# Miniproj.net
KiCad netlist of a schematic drawn in Altium Designer
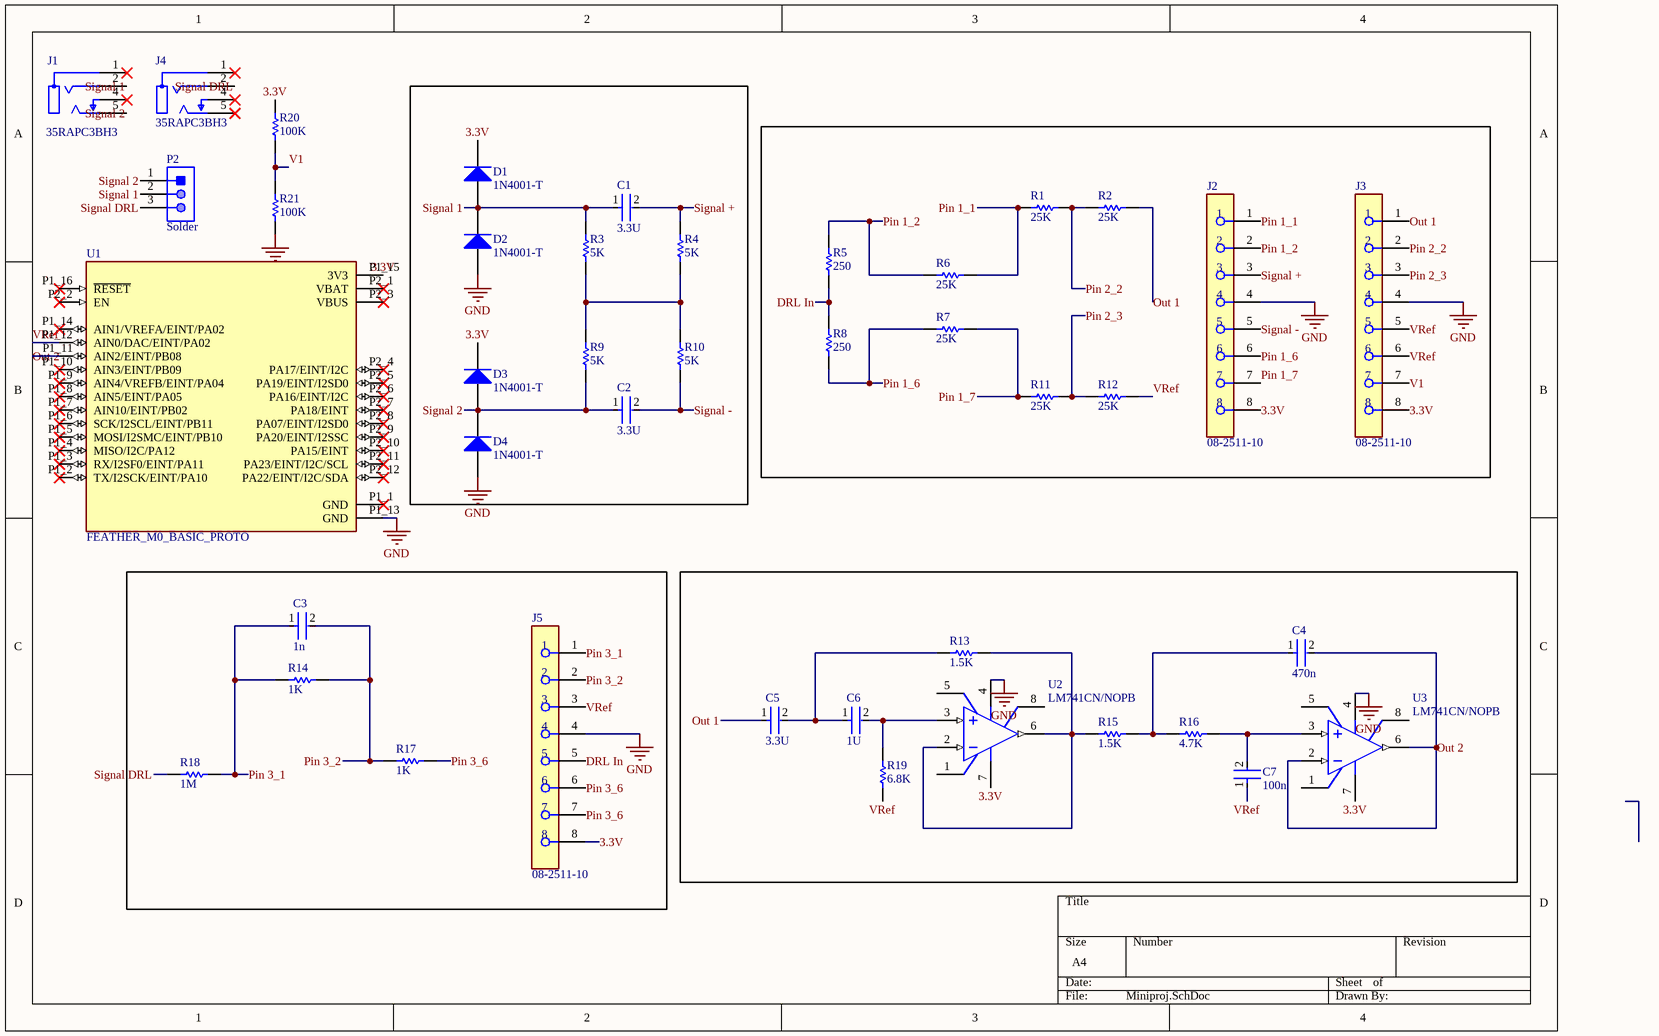
[diagram p0: Miniproj.SchDoc]

(export (version "E")
  (design (tool "Eeschema 10.0.6"))
  (components
    (comp (ref "C1")
      (value "3.3U")
      (footprint "FP-RCE3DB-MFG")
      (description "Cap Ceramic 10uF 25V X7R ±10% Radial 2.5mm +125°C Automotive Ammo Pack")
      (fields (field (name "TOLERANCE") "10%"))
      (libsource (lib "Altium Content Vault") (part "b4654b650e69147ec39a6b967a45e02"))
    )
    (comp (ref "C2")
      (value "3.3U")
      (footprint "FP-RCE3DB-MFG")
      (description "Cap Ceramic 10uF 25V X7R ±10% Radial 2.5mm +125°C Automotive Ammo Pack")
      (fields (field (name "TOLERANCE") "10%"))
      (libsource (lib "Altium Content Vault") (part "b4654b650e69147ec39a6b967a45e02"))
    )
    (comp (ref "C3")
      (value "1n")
      (footprint "FP-RCE3DB-MFG")
      (description "Cap Ceramic 10uF 25V X7R ±10% Radial 2.5mm +125°C Automotive Ammo Pack")
      (fields (field (name "TOLERANCE") "10%"))
      (libsource (lib "Altium Content Vault") (part "b4654b650e69147ec39a6b967a45e02"))
    )
    (comp (ref "C4")
      (value "470n")
      (footprint "FP-RCE3DB-MFG")
      (description "Cap Ceramic 10uF 25V X7R ±10% Radial 2.5mm +125°C Automotive Ammo Pack")
      (fields (field (name "TOLERANCE") "10%"))
      (libsource (lib "Altium Content Vault") (part "b4654b650e69147ec39a6b967a45e02"))
    )
    (comp (ref "C5")
      (value "3.3U")
      (footprint "FP-RCE3DB-MFG")
      (description "Cap Ceramic 10uF 25V X7R ±10% Radial 2.5mm +125°C Automotive Ammo Pack")
      (fields (field (name "TOLERANCE") "10%"))
      (libsource (lib "Altium Content Vault") (part "b4654b650e69147ec39a6b967a45e02"))
    )
    (comp (ref "C6")
      (value "1U")
      (footprint "FP-RCE3DB-MFG")
      (description "Cap Ceramic 10uF 25V X7R ±10% Radial 2.5mm +125°C Automotive Ammo Pack")
      (fields (field (name "TOLERANCE") "10%"))
      (libsource (lib "Altium Content Vault") (part "b4654b650e69147ec39a6b967a45e02"))
    )
    (comp (ref "C7")
      (value "100n")
      (footprint "FP-RCE3DB-MFG")
      (description "Cap Ceramic 10uF 25V X7R ±10% Radial 2.5mm +125°C Automotive Ammo Pack")
      (fields (field (name "TOLERANCE") "10%"))
      (libsource (lib "Altium Content Vault") (part "b4654b650e69147ec39a6b967a45e02"))
    )
    (comp (ref "D1")
      (value "1N4001-T")
      (footprint "DIOD-DO-41-P-2_V")
      (description "1.0 A Rectifier, 15 pF, 50 V, -65 to 150 degC, 2-Pin DO-41 Plastic, RoHS, Tape and Reel")
      (fields (field (name "MANUFACTURER") "Diodes Inc"))
      (libsource (lib "Altium Content Vault") (part "DIOD-D-A1K2-2"))
    )
    (comp (ref "D2")
      (value "1N4001-T")
      (footprint "DIOD-DO-41-P-2_V")
      (description "1.0 A Rectifier, 15 pF, 50 V, -65 to 150 degC, 2-Pin DO-41 Plastic, RoHS, Tape and Reel")
      (fields (field (name "MANUFACTURER") "Diodes Inc"))
      (libsource (lib "Altium Content Vault") (part "DIOD-D-A1K2-2"))
    )
    (comp (ref "D3")
      (value "1N4001-T")
      (footprint "DIOD-DO-41-P-2_V")
      (description "1.0 A Rectifier, 15 pF, 50 V, -65 to 150 degC, 2-Pin DO-41 Plastic, RoHS, Tape and Reel")
      (fields (field (name "MANUFACTURER") "Diodes Inc"))
      (libsource (lib "Altium Content Vault") (part "DIOD-D-A1K2-2"))
    )
    (comp (ref "D4")
      (value "1N4001-T")
      (footprint "DIOD-DO-41-P-2_V")
      (description "1.0 A Rectifier, 15 pF, 50 V, -65 to 150 degC, 2-Pin DO-41 Plastic, RoHS, Tape and Reel")
      (fields (field (name "MANUFACTURER") "Diodes Inc"))
      (libsource (lib "Altium Content Vault") (part "DIOD-D-A1K2-2"))
    )
    (comp (ref "J1")
      (value "35RAPC3BH3")
      (footprint "FP-35RAPC3BH3-MFG")
      (description "CONN JACK STEREO 3.5MM R/A")
      (libsource (lib "Altium Content Vault") (part "6593a1246df2d7246a2ad7da18ee256"))
    )
    (comp (ref "J2")
      (value "08-2511-10")
      (footprint "FP-08-2511-10-MFG")
      (description "CONN IC DIP SOCKET 8POS TIN")
      (fields
        (field (name "MANUFACTURER") "Aries Electronics")
        (field (name "OCTOPART") "https://octopart.com/08-2511-10-aries-767661")
      )
      (libsource (lib "Altium Content Vault") (part "b0a0b555dd3abf3683e7c330df25cc4"))
    )
    (comp (ref "J3")
      (value "08-2511-10")
      (footprint "FP-08-2511-10-MFG")
      (description "CONN IC DIP SOCKET 8POS TIN")
      (fields
        (field (name "MANUFACTURER") "Aries Electronics")
        (field (name "OCTOPART") "https://octopart.com/08-2511-10-aries-767661")
      )
      (libsource (lib "Altium Content Vault") (part "b0a0b555dd3abf3683e7c330df25cc4"))
    )
    (comp (ref "J4")
      (value "35RAPC3BH3")
      (footprint "FP-35RAPC3BH3-MFG")
      (description "CONN JACK STEREO 3.5MM R/A")
      (libsource (lib "Altium Content Vault") (part "6593a1246df2d7246a2ad7da18ee256"))
    )
    (comp (ref "J5")
      (value "08-2511-10")
      (footprint "FP-08-2511-10-MFG")
      (description "CONN IC DIP SOCKET 8POS TIN")
      (fields
        (field (name "MANUFACTURER") "Aries Electronics")
        (field (name "OCTOPART") "https://octopart.com/08-2511-10-aries-767661")
      )
      (libsource (lib "Altium Content Vault") (part "b0a0b555dd3abf3683e7c330df25cc4"))
    )
    (comp (ref "P2")
      (value "Solder")
      (footprint "JST-B3B-PH-K-S-3_V")
      (fields (field (name "MANUFACTURER") "JST"))
      (libsource (lib "Altium Content Vault") (part "CN-1P-M-R3"))
    )
    (comp (ref "R1")
      (value "25K")
      (footprint "RESA60-630X240")
      (description "Axial Resistor, 1 KOhm, +/- 1%, 250 mW, -55 to 155 degC, 2-Pin THD, RoHS, Bulk")
      (fields (field (name "TOLERANCE") "1%"))
      (libsource (lib "Altium Content Vault") (part "RES-2"))
    )
    (comp (ref "R2")
      (value "25K")
      (footprint "RESA60-630X240")
      (description "Axial Resistor, 1 KOhm, +/- 1%, 250 mW, -55 to 155 degC, 2-Pin THD, RoHS, Bulk")
      (fields (field (name "TOLERANCE") "1%"))
      (libsource (lib "Altium Content Vault") (part "RES-2"))
    )
    (comp (ref "R3")
      (value "5K")
      (footprint "RESA60-630X240")
      (description "Axial Resistor, 1 KOhm, +/- 1%, 250 mW, -55 to 155 degC, 2-Pin THD, RoHS, Bulk")
      (fields (field (name "TOLERANCE") "1%"))
      (libsource (lib "Altium Content Vault") (part "RES-2"))
    )
    (comp (ref "R4")
      (value "5K")
      (footprint "RESA60-630X240")
      (description "Axial Resistor, 1 KOhm, +/- 1%, 250 mW, -55 to 155 degC, 2-Pin THD, RoHS, Bulk")
      (fields (field (name "TOLERANCE") "1%"))
      (libsource (lib "Altium Content Vault") (part "RES-2"))
    )
    (comp (ref "R5")
      (value "250")
      (footprint "RESA60-630X240")
      (description "Axial Resistor, 1 KOhm, +/- 1%, 250 mW, -55 to 155 degC, 2-Pin THD, RoHS, Bulk")
      (fields (field (name "TOLERANCE") "1%"))
      (libsource (lib "Altium Content Vault") (part "RES-2"))
    )
    (comp (ref "R6")
      (value "25K")
      (footprint "RESA60-630X240")
      (description "Axial Resistor, 1 KOhm, +/- 1%, 250 mW, -55 to 155 degC, 2-Pin THD, RoHS, Bulk")
      (fields (field (name "TOLERANCE") "1%"))
      (libsource (lib "Altium Content Vault") (part "RES-2"))
    )
    (comp (ref "R7")
      (value "25K")
      (footprint "RESA60-630X240")
      (description "Axial Resistor, 1 KOhm, +/- 1%, 250 mW, -55 to 155 degC, 2-Pin THD, RoHS, Bulk")
      (fields (field (name "TOLERANCE") "1%"))
      (libsource (lib "Altium Content Vault") (part "RES-2"))
    )
    (comp (ref "R8")
      (value "250")
      (footprint "RESA60-630X240")
      (description "Axial Resistor, 1 KOhm, +/- 1%, 250 mW, -55 to 155 degC, 2-Pin THD, RoHS, Bulk")
      (fields (field (name "TOLERANCE") "1%"))
      (libsource (lib "Altium Content Vault") (part "RES-2"))
    )
    (comp (ref "R9")
      (value "5K")
      (footprint "RESA60-630X240")
      (description "Axial Resistor, 1 KOhm, +/- 1%, 250 mW, -55 to 155 degC, 2-Pin THD, RoHS, Bulk")
      (fields (field (name "TOLERANCE") "1%"))
      (libsource (lib "Altium Content Vault") (part "RES-2"))
    )
    (comp (ref "R10")
      (value "5K")
      (footprint "RESA60-630X240")
      (description "Axial Resistor, 1 KOhm, +/- 1%, 250 mW, -55 to 155 degC, 2-Pin THD, RoHS, Bulk")
      (fields (field (name "TOLERANCE") "1%"))
      (libsource (lib "Altium Content Vault") (part "RES-2"))
    )
    (comp (ref "R11")
      (value "25K")
      (footprint "RESA60-630X240")
      (description "Axial Resistor, 1 KOhm, +/- 1%, 250 mW, -55 to 155 degC, 2-Pin THD, RoHS, Bulk")
      (fields (field (name "TOLERANCE") "1%"))
      (libsource (lib "Altium Content Vault") (part "RES-2"))
    )
    (comp (ref "R12")
      (value "25K")
      (footprint "RESA60-630X240")
      (description "Axial Resistor, 1 KOhm, +/- 1%, 250 mW, -55 to 155 degC, 2-Pin THD, RoHS, Bulk")
      (fields (field (name "TOLERANCE") "1%"))
      (libsource (lib "Altium Content Vault") (part "RES-2"))
    )
    (comp (ref "R13")
      (value "1.5K")
      (footprint "RESA60-630X240")
      (description "Axial Resistor, 1 KOhm, +/- 1%, 250 mW, -55 to 155 degC, 2-Pin THD, RoHS, Bulk")
      (fields (field (name "TOLERANCE") "1%"))
      (libsource (lib "Altium Content Vault") (part "RES-2"))
    )
    (comp (ref "R14")
      (value "1K")
      (footprint "RESA60-630X240")
      (description "Axial Resistor, 1 KOhm, +/- 1%, 250 mW, -55 to 155 degC, 2-Pin THD, RoHS, Bulk")
      (fields (field (name "TOLERANCE") "1%"))
      (libsource (lib "Altium Content Vault") (part "RES-2"))
    )
    (comp (ref "R15")
      (value "1.5K")
      (footprint "RESA60-630X240")
      (description "Axial Resistor, 1 KOhm, +/- 1%, 250 mW, -55 to 155 degC, 2-Pin THD, RoHS, Bulk")
      (fields (field (name "TOLERANCE") "1%"))
      (libsource (lib "Altium Content Vault") (part "RES-2"))
    )
    (comp (ref "R16")
      (value "4.7K")
      (footprint "RESA60-630X240")
      (description "Axial Resistor, 1 KOhm, +/- 1%, 250 mW, -55 to 155 degC, 2-Pin THD, RoHS, Bulk")
      (fields (field (name "TOLERANCE") "1%"))
      (libsource (lib "Altium Content Vault") (part "RES-2"))
    )
    (comp (ref "R17")
      (value "1K")
      (footprint "RESA60-630X240")
      (description "Axial Resistor, 1 KOhm, +/- 1%, 250 mW, -55 to 155 degC, 2-Pin THD, RoHS, Bulk")
      (fields (field (name "TOLERANCE") "1%"))
      (libsource (lib "Altium Content Vault") (part "RES-2"))
    )
    (comp (ref "R18")
      (value "1M")
      (footprint "RESA60-630X240")
      (description "Axial Resistor, 1 KOhm, +/- 1%, 250 mW, -55 to 155 degC, 2-Pin THD, RoHS, Bulk")
      (fields (field (name "TOLERANCE") "1%"))
      (libsource (lib "Altium Content Vault") (part "RES-2"))
    )
    (comp (ref "R19")
      (value "6.8K")
      (footprint "RESA60-630X240")
      (description "Axial Resistor, 1 KOhm, +/- 1%, 250 mW, -55 to 155 degC, 2-Pin THD, RoHS, Bulk")
      (fields (field (name "TOLERANCE") "1%"))
      (libsource (lib "Altium Content Vault") (part "RES-2"))
    )
    (comp (ref "R20")
      (value "100K")
      (footprint "RESA60-630X240")
      (description "Axial Resistor, 1 KOhm, +/- 1%, 250 mW, -55 to 155 degC, 2-Pin THD, RoHS, Bulk")
      (fields (field (name "TOLERANCE") "1%"))
      (libsource (lib "Altium Content Vault") (part "RES-2"))
    )
    (comp (ref "R21")
      (value "100K")
      (footprint "RESA60-630X240")
      (description "Axial Resistor, 1 KOhm, +/- 1%, 250 mW, -55 to 155 degC, 2-Pin THD, RoHS, Bulk")
      (fields (field (name "TOLERANCE") "1%"))
      (libsource (lib "Altium Content Vault") (part "RES-2"))
    )
    (comp (ref "U1")
      (value "FEATHER_M0_BASIC_PROTO")
      (footprint "MODULE_FEATHER_M0_BASIC_PROTO")
      (description "ATSAMD21G18 Feather M0 Basic Proto series ARM® Cortex®-M0+ MCU 32-Bit Embedded Evaluation Board")
      (fields (field (name "MF") "Adafruit Industries") (field (name "MP") "Feather M0 Basic Proto"))
      (libsource (lib "mini_project_one_rail") (part "CMP-003-000000-1"))
    )
    (comp (ref "U2")
      (value "LM741CN/NOPB")
      (footprint "P0008A")
      (description "Operational Amplifier, 8-pin MDIP, Pb-Free")
      (fields (field (name "MANUFACTURER") "Texas Instruments"))
      (libsource (lib "Altium Content Vault") (part "AMP-OPA-LM741-8"))
    )
    (comp (ref "U3")
      (value "LM741CN/NOPB")
      (footprint "P0008A")
      (description "Operational Amplifier, 8-pin MDIP, Pb-Free")
      (fields (field (name "MANUFACTURER") "Texas Instruments"))
      (libsource (lib "Altium Content Vault") (part "AMP-OPA-LM741-8"))
    )
  )
  (nets
    (net (code "1") (name "/3.3V") (class "Default")
      (node (ref "D1") (pin "2") (pinfunction "K_2") (pintype "passive"))
      (node (ref "D3") (pin "2") (pinfunction "K_2") (pintype "passive"))
      (node (ref "J2") (pin "8") (pinfunction "8_8") (pintype "passive"))
      (node (ref "J3") (pin "8") (pinfunction "8_8") (pintype "passive"))
      (node (ref "J5") (pin "8") (pinfunction "8_8") (pintype "passive"))
      (node (ref "R20") (pin "2") (pinfunction "2_2") (pintype "passive"))
      (node (ref "U1") (pin "P1_15") (pinfunction "3V3_P1_15") (pintype "power_in"))
      (node (ref "U2") (pin "7") (pinfunction "V+_7") (pintype "power_in"))
      (node (ref "U3") (pin "7") (pinfunction "V+_7") (pintype "power_in"))
    )
    (net (code "2") (name "/DRL In") (class "Default")
      (node (ref "J5") (pin "5") (pinfunction "5_5") (pintype "passive"))
      (node (ref "R5") (pin "2") (pinfunction "2_2") (pintype "passive"))
      (node (ref "R8") (pin "1") (pinfunction "1_1") (pintype "passive"))
    )
    (net (code "3") (name "/Out 1") (class "Default")
      (node (ref "C5") (pin "1") (pinfunction "1_1") (pintype "passive"))
      (node (ref "J3") (pin "1") (pinfunction "1_1") (pintype "passive"))
      (node (ref "R2") (pin "1") (pinfunction "1_1") (pintype "passive"))
    )
    (net (code "4") (name "/Out 2") (class "Default")
      (node (ref "C4") (pin "2") (pinfunction "2_2") (pintype "passive"))
      (node (ref "U1") (pin "P1_11") (pinfunction "AIN2/EINT/PB08_P1_11") (pintype "bidirectional"))
      (node (ref "U3") (pin "2") (pinfunction "IN-_2") (pintype "input"))
      (node (ref "U3") (pin "6") (pinfunction "OUT_6") (pintype "output"))
    )
    (net (code "5") (name "/Pin 1_1") (class "Default")
      (node (ref "J2") (pin "1") (pinfunction "1_1") (pintype "passive"))
      (node (ref "R1") (pin "2") (pinfunction "2_2") (pintype "passive"))
      (node (ref "R6") (pin "1") (pinfunction "1_1") (pintype "passive"))
    )
    (net (code "6") (name "/Pin 1_2") (class "Default")
      (node (ref "J2") (pin "2") (pinfunction "2_2") (pintype "passive"))
      (node (ref "R5") (pin "1") (pinfunction "1_1") (pintype "passive"))
      (node (ref "R6") (pin "2") (pinfunction "2_2") (pintype "passive"))
    )
    (net (code "7") (name "/Pin 1_6") (class "Default")
      (node (ref "J2") (pin "6") (pinfunction "6_6") (pintype "passive"))
      (node (ref "R7") (pin "2") (pinfunction "2_2") (pintype "passive"))
      (node (ref "R8") (pin "2") (pinfunction "2_2") (pintype "passive"))
    )
    (net (code "8") (name "/Pin 1_7") (class "Default")
      (node (ref "J2") (pin "7") (pinfunction "7_7") (pintype "passive"))
      (node (ref "R11") (pin "2") (pinfunction "2_2") (pintype "passive"))
      (node (ref "R7") (pin "1") (pinfunction "1_1") (pintype "passive"))
    )
    (net (code "9") (name "/Pin 2_2") (class "Default")
      (node (ref "J3") (pin "2") (pinfunction "2_2") (pintype "passive"))
      (node (ref "R1") (pin "1") (pinfunction "1_1") (pintype "passive"))
      (node (ref "R2") (pin "2") (pinfunction "2_2") (pintype "passive"))
    )
    (net (code "10") (name "/Pin 2_3") (class "Default")
      (node (ref "J3") (pin "3") (pinfunction "3_3") (pintype "passive"))
      (node (ref "R11") (pin "1") (pinfunction "1_1") (pintype "passive"))
      (node (ref "R12") (pin "2") (pinfunction "2_2") (pintype "passive"))
    )
    (net (code "11") (name "/Pin 3_1") (class "Default")
      (node (ref "C3") (pin "1") (pinfunction "1_1") (pintype "passive"))
      (node (ref "J5") (pin "1") (pinfunction "1_1") (pintype "passive"))
      (node (ref "R14") (pin "2") (pinfunction "2_2") (pintype "passive"))
      (node (ref "R18") (pin "1") (pinfunction "1_1") (pintype "passive"))
    )
    (net (code "12") (name "/Pin 3_2") (class "Default")
      (node (ref "C3") (pin "2") (pinfunction "2_2") (pintype "passive"))
      (node (ref "J5") (pin "2") (pinfunction "2_2") (pintype "passive"))
      (node (ref "R14") (pin "1") (pinfunction "1_1") (pintype "passive"))
      (node (ref "R17") (pin "2") (pinfunction "2_2") (pintype "passive"))
    )
    (net (code "13") (name "/Pin 3_6") (class "Default")
      (node (ref "J5") (pin "6") (pinfunction "6_6") (pintype "passive"))
      (node (ref "J5") (pin "7") (pinfunction "7_7") (pintype "passive"))
      (node (ref "R17") (pin "1") (pinfunction "1_1") (pintype "passive"))
    )
    (net (code "14") (name "/Signal +") (class "Default")
      (node (ref "C1") (pin "2") (pinfunction "2_2") (pintype "passive"))
      (node (ref "J2") (pin "3") (pinfunction "3_3") (pintype "passive"))
      (node (ref "R4") (pin "2") (pinfunction "2_2") (pintype "passive"))
    )
    (net (code "15") (name "/Signal -") (class "Default")
      (node (ref "C2") (pin "2") (pinfunction "2_2") (pintype "passive"))
      (node (ref "J2") (pin "5") (pinfunction "5_5") (pintype "passive"))
      (node (ref "R10") (pin "1") (pinfunction "1_1") (pintype "passive"))
    )
    (net (code "16") (name "/Signal 1") (class "Default")
      (node (ref "C1") (pin "1") (pinfunction "1_1") (pintype "passive"))
      (node (ref "D1") (pin "1") (pinfunction "A_1") (pintype "passive"))
      (node (ref "D2") (pin "2") (pinfunction "K_2") (pintype "passive"))
      (node (ref "J1") (pin "2") (pinfunction "2_2") (pintype "passive"))
      (node (ref "P2") (pin "2") (pinfunction "2_2") (pintype "passive"))
      (node (ref "R3") (pin "2") (pinfunction "2_2") (pintype "passive"))
    )
    (net (code "17") (name "/Signal 2") (class "Default")
      (node (ref "C2") (pin "1") (pinfunction "1_1") (pintype "passive"))
      (node (ref "D3") (pin "1") (pinfunction "A_1") (pintype "passive"))
      (node (ref "D4") (pin "2") (pinfunction "K_2") (pintype "passive"))
      (node (ref "J1") (pin "5") (pinfunction "5_5") (pintype "passive"))
      (node (ref "P2") (pin "1") (pinfunction "1_1") (pintype "passive"))
      (node (ref "R9") (pin "1") (pinfunction "1_1") (pintype "passive"))
    )
    (net (code "18") (name "/Signal DRL") (class "Default")
      (node (ref "J4") (pin "2") (pinfunction "2_2") (pintype "passive"))
      (node (ref "P2") (pin "3") (pinfunction "3_3") (pintype "passive"))
      (node (ref "R18") (pin "2") (pinfunction "2_2") (pintype "passive"))
    )
    (net (code "19") (name "/V1") (class "Default")
      (node (ref "J3") (pin "7") (pinfunction "7_7") (pintype "passive"))
      (node (ref "R20") (pin "1") (pinfunction "1_1") (pintype "passive"))
      (node (ref "R21") (pin "2") (pinfunction "2_2") (pintype "passive"))
    )
    (net (code "20") (name "/VRef") (class "Default")
      (node (ref "C7") (pin "1") (pinfunction "1_1") (pintype "passive"))
      (node (ref "J3") (pin "5") (pinfunction "5_5") (pintype "passive"))
      (node (ref "J3") (pin "6") (pinfunction "6_6") (pintype "passive"))
      (node (ref "J5") (pin "3") (pinfunction "3_3") (pintype "passive"))
      (node (ref "R12") (pin "1") (pinfunction "1_1") (pintype "passive"))
      (node (ref "R19") (pin "2") (pinfunction "2_2") (pintype "passive"))
      (node (ref "U1") (pin "P1_12") (pinfunction "AIN0/DAC/EINT/PA02_P1_12") (pintype "bidirectional"))
    )
    (net (code "21") (name "GND") (class "Default")
      (node (ref "D2") (pin "1") (pinfunction "A_1") (pintype "passive"))
      (node (ref "D4") (pin "1") (pinfunction "A_1") (pintype "passive"))
      (node (ref "J2") (pin "4") (pinfunction "4_4") (pintype "passive"))
      (node (ref "J3") (pin "4") (pinfunction "4_4") (pintype "passive"))
      (node (ref "J5") (pin "4") (pinfunction "4_4") (pintype "passive"))
      (node (ref "R21") (pin "1") (pinfunction "1_1") (pintype "passive"))
      (node (ref "U1") (pin "P1_13") (pinfunction "GND_P1_13") (pintype "power_in"))
      (node (ref "U2") (pin "4") (pinfunction "V-_4") (pintype "power_in"))
      (node (ref "U3") (pin "4") (pinfunction "V-_4") (pintype "power_in"))
    )
    (net (code "22") (name "Net-(C4-Pad1)") (class "Default")
      (node (ref "C4") (pin "1") (pinfunction "1_1") (pintype "passive"))
      (node (ref "R15") (pin "1") (pinfunction "1_1") (pintype "passive"))
      (node (ref "R16") (pin "2") (pinfunction "2_2") (pintype "passive"))
    )
    (net (code "23") (name "Net-(C5-Pad2)") (class "Default")
      (node (ref "C5") (pin "2") (pinfunction "2_2") (pintype "passive"))
      (node (ref "C6") (pin "1") (pinfunction "1_1") (pintype "passive"))
      (node (ref "R13") (pin "2") (pinfunction "2_2") (pintype "passive"))
    )
    (net (code "24") (name "Net-(R10-Pad2)") (class "Default")
      (node (ref "R10") (pin "2") (pinfunction "2_2") (pintype "passive"))
      (node (ref "R3") (pin "1") (pinfunction "1_1") (pintype "passive"))
      (node (ref "R4") (pin "1") (pinfunction "1_1") (pintype "passive"))
      (node (ref "R9") (pin "2") (pinfunction "2_2") (pintype "passive"))
    )
    (net (code "25") (name "Net-(U2-IN+)") (class "Default")
      (node (ref "C6") (pin "2") (pinfunction "2_2") (pintype "passive"))
      (node (ref "R19") (pin "1") (pinfunction "1_1") (pintype "passive"))
      (node (ref "U2") (pin "3") (pinfunction "IN+_3") (pintype "input"))
    )
    (net (code "26") (name "Net-(U2-IN-)") (class "Default")
      (node (ref "R13") (pin "1") (pinfunction "1_1") (pintype "passive"))
      (node (ref "R15") (pin "2") (pinfunction "2_2") (pintype "passive"))
      (node (ref "U2") (pin "2") (pinfunction "IN-_2") (pintype "input"))
      (node (ref "U2") (pin "6") (pinfunction "OUT_6") (pintype "output"))
    )
    (net (code "27") (name "Net-(U3-IN+)") (class "Default")
      (node (ref "C7") (pin "2") (pinfunction "2_2") (pintype "passive"))
      (node (ref "R16") (pin "1") (pinfunction "1_1") (pintype "passive"))
      (node (ref "U3") (pin "3") (pinfunction "IN+_3") (pintype "input"))
    )
    (net (code "28") (name "unconnected-(J1-Pad1)") (class "Default")
      (node (ref "J1") (pin "1") (pinfunction "1_1") (pintype "passive+no_connect"))
    )
    (net (code "29") (name "unconnected-(J1-Pad4)") (class "Default")
      (node (ref "J1") (pin "4") (pinfunction "4_4") (pintype "passive+no_connect"))
    )
    (net (code "30") (name "unconnected-(J4-Pad1)") (class "Default")
      (node (ref "J4") (pin "1") (pinfunction "1_1") (pintype "passive+no_connect"))
    )
    (net (code "31") (name "unconnected-(J4-Pad4)") (class "Default")
      (node (ref "J4") (pin "4") (pinfunction "4_4") (pintype "passive+no_connect"))
    )
    (net (code "32") (name "unconnected-(J4-Pad5)") (class "Default")
      (node (ref "J4") (pin "5") (pinfunction "5_5") (pintype "passive+no_connect"))
    )
    (net (code "33") (name "unconnected-(U1-AIN1{slash}VREFA{slash}EINT{slash}PA02-PadP1_14)") (class "Default")
      (node (ref "U1") (pin "P1_14") (pinfunction "AIN1/VREFA/EINT/PA02_P1_14") (pintype "bidirectional+no_connect"))
    )
    (net (code "34") (name "unconnected-(U1-AIN3{slash}EINT{slash}PB09-PadP1_10)") (class "Default")
      (node (ref "U1") (pin "P1_10") (pinfunction "AIN3/EINT/PB09_P1_10") (pintype "bidirectional+no_connect"))
    )
    (net (code "35") (name "unconnected-(U1-AIN4{slash}VREFB{slash}EINT{slash}PA04-PadP1_9)") (class "Default")
      (node (ref "U1") (pin "P1_9") (pinfunction "AIN4/VREFB/EINT/PA04_P1_9") (pintype "bidirectional+no_connect"))
    )
    (net (code "36") (name "unconnected-(U1-AIN5{slash}EINT{slash}PA05-PadP1_8)") (class "Default")
      (node (ref "U1") (pin "P1_8") (pinfunction "AIN5/EINT/PA05_P1_8") (pintype "bidirectional+no_connect"))
    )
    (net (code "37") (name "unconnected-(U1-AIN10{slash}EINT{slash}PB02-PadP1_7)") (class "Default")
      (node (ref "U1") (pin "P1_7") (pinfunction "AIN10/EINT/PB02_P1_7") (pintype "bidirectional+no_connect"))
    )
    (net (code "38") (name "unconnected-(U1-EN-PadP2_2)") (class "Default")
      (node (ref "U1") (pin "P2_2") (pinfunction "EN_P2_2") (pintype "input+no_connect"))
    )
    (net (code "39") (name "unconnected-(U1-GND-PadP1_1)") (class "Default")
      (node (ref "U1") (pin "P1_1") (pinfunction "GND_P1_1") (pintype "power_in+no_connect"))
    )
    (net (code "40") (name "unconnected-(U1-MISO{slash}I2C{slash}PA12-PadP1_4)") (class "Default")
      (node (ref "U1") (pin "P1_4") (pinfunction "MISO/I2C/PA12_P1_4") (pintype "bidirectional+no_connect"))
    )
    (net (code "41") (name "unconnected-(U1-MOSI{slash}I2SMC{slash}EINT{slash}PB10-PadP1_5)") (class "Default")
      (node (ref "U1") (pin "P1_5") (pinfunction "MOSI/I2SMC/EINT/PB10_P1_5") (pintype "bidirectional+no_connect"))
    )
    (net (code "42") (name "unconnected-(U1-PA07{slash}EINT{slash}I2SD0-PadP2_8)") (class "Default")
      (node (ref "U1") (pin "P2_8") (pinfunction "PA07/EINT/I2SD0_P2_8") (pintype "bidirectional+no_connect"))
    )
    (net (code "43") (name "unconnected-(U1-PA15{slash}EINT-PadP2_10)") (class "Default")
      (node (ref "U1") (pin "P2_10") (pinfunction "PA15/EINT_P2_10") (pintype "bidirectional+no_connect"))
    )
    (net (code "44") (name "unconnected-(U1-PA16{slash}EINT{slash}I2C-PadP2_6)") (class "Default")
      (node (ref "U1") (pin "P2_6") (pinfunction "PA16/EINT/I2C_P2_6") (pintype "bidirectional+no_connect"))
    )
    (net (code "45") (name "unconnected-(U1-PA17{slash}EINT{slash}I2C-PadP2_4)") (class "Default")
      (node (ref "U1") (pin "P2_4") (pinfunction "PA17/EINT/I2C_P2_4") (pintype "bidirectional+no_connect"))
    )
    (net (code "46") (name "unconnected-(U1-PA18{slash}EINT-PadP2_7)") (class "Default")
      (node (ref "U1") (pin "P2_7") (pinfunction "PA18/EINT_P2_7") (pintype "bidirectional+no_connect"))
    )
    (net (code "47") (name "unconnected-(U1-PA19{slash}EINT{slash}I2SD0-PadP2_5)") (class "Default")
      (node (ref "U1") (pin "P2_5") (pinfunction "PA19/EINT/I2SD0_P2_5") (pintype "bidirectional+no_connect"))
    )
    (net (code "48") (name "unconnected-(U1-PA20{slash}EINT{slash}I2SSC-PadP2_9)") (class "Default")
      (node (ref "U1") (pin "P2_9") (pinfunction "PA20/EINT/I2SSC_P2_9") (pintype "bidirectional+no_connect"))
    )
    (net (code "49") (name "unconnected-(U1-PA22{slash}EINT{slash}I2C{slash}SDA-PadP2_12)") (class "Default")
      (node (ref "U1") (pin "P2_12") (pinfunction "PA22/EINT/I2C/SDA_P2_12") (pintype "bidirectional+no_connect"))
    )
    (net (code "50") (name "unconnected-(U1-PA23{slash}EINT{slash}I2C{slash}SCL-PadP2_11)") (class "Default")
      (node (ref "U1") (pin "P2_11") (pinfunction "PA23/EINT/I2C/SCL_P2_11") (pintype "bidirectional+no_connect"))
    )
    (net (code "51") (name "unconnected-(U1-RX{slash}I2SF0{slash}EINT{slash}PA11-PadP1_3)") (class "Default")
      (node (ref "U1") (pin "P1_3") (pinfunction "RX/I2SF0/EINT/PA11_P1_3") (pintype "bidirectional+no_connect"))
    )
    (net (code "52") (name "unconnected-(U1-SCK{slash}I2SCL{slash}EINT{slash}PB11-PadP1_6)") (class "Default")
      (node (ref "U1") (pin "P1_6") (pinfunction "SCK/I2SCL/EINT/PB11_P1_6") (pintype "bidirectional+no_connect"))
    )
    (net (code "53") (name "unconnected-(U1-TX{slash}I2SCK{slash}EINT{slash}PA10-PadP1_2)") (class "Default")
      (node (ref "U1") (pin "P1_2") (pinfunction "TX/I2SCK/EINT/PA10_P1_2") (pintype "bidirectional+no_connect"))
    )
    (net (code "54") (name "unconnected-(U1-VBAT-PadP2_1)") (class "Default")
      (node (ref "U1") (pin "P2_1") (pinfunction "VBAT_P2_1") (pintype "power_in+no_connect"))
    )
    (net (code "55") (name "unconnected-(U1-VBUS-PadP2_3)") (class "Default")
      (node (ref "U1") (pin "P2_3") (pinfunction "VBUS_P2_3") (pintype "power_in+no_connect"))
    )
    (net (code "56") (name "unconnected-(U1-~{RESET}-PadP1_16)") (class "Default")
      (node (ref "U1") (pin "P1_16") (pinfunction "~{RESET}_P1_16") (pintype "input+no_connect"))
    )
    (net (code "57") (name "unconnected-(U2-NC-Pad8)") (class "Default")
      (node (ref "U2") (pin "8") (pinfunction "NC_8") (pintype "passive"))
    )
    (net (code "58") (name "unconnected-(U2-OFS_NULL-Pad1)") (class "Default")
      (node (ref "U2") (pin "1") (pinfunction "OFS_NULL_1") (pintype "passive"))
    )
    (net (code "59") (name "unconnected-(U2-OFS_NULL-Pad5)") (class "Default")
      (node (ref "U2") (pin "5") (pinfunction "OFS_NULL_5") (pintype "passive"))
    )
    (net (code "60") (name "unconnected-(U3-NC-Pad8)") (class "Default")
      (node (ref "U3") (pin "8") (pinfunction "NC_8") (pintype "passive"))
    )
    (net (code "61") (name "unconnected-(U3-OFS_NULL-Pad1)") (class "Default")
      (node (ref "U3") (pin "1") (pinfunction "OFS_NULL_1") (pintype "passive"))
    )
    (net (code "62") (name "unconnected-(U3-OFS_NULL-Pad5)") (class "Default")
      (node (ref "U3") (pin "5") (pinfunction "OFS_NULL_5") (pintype "passive"))
    )
  )
)
